# schematic_flex_sensor_driver.net
KiCad netlist of a schematic drawn in EAGLE
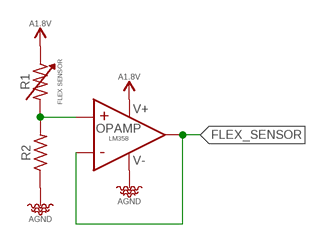
[diagram p0: schematic, sheet 1]

(export (version "E")
  (design (tool "Eeschema 10.0.6"))
  (components
    (comp (ref "OPAMP")
      (value "OPAMP_ILLUSTRATIVE")
      (footprint "eagle-import:SOT95P280X145-5")
      (libsource (lib "eagle-import") (part "OPAMP_ILLUSTRATIVE"))
    )
    (comp (ref "R1")
      (value "FLEX SENSOR")
      (footprint "eagle-import:PTH-CONNECTOR-2PIN")
      (fields
        (field (name "MFR") "TT Electronics/BI")
        (field (name "MPN") "P160KN2-0QA25B10K")
        (field (name "CREATOR") "MrSwirlyEyes")
      )
      (libsource (lib "eagle-import") (part "VARIABLE_PTH_10K-1/5W-20%_ACTLEN-25_OFFBOARD"))
    )
    (comp (ref "R2")
      (value "10K")
      (footprint "eagle-import:RESC1005X35_SMD-0402")
      (fields (field (name "MFR") "Yageo") (field (name "MPN") "RC0402JR-0710KP"))
      (libsource (lib "eagle-import") (part "10KΩ_SMD-0402_1/16W-5%"))
    )
  )
  (nets
    (net (code "1") (name "A1.8V") (class "Default")
      (node (ref "OPAMP") (pin "4") (pinfunction "V+_4") (pintype "passive"))
      (node (ref "R1") (pin "1") (pinfunction "1_1") (pintype "passive"))
    )
    (net (code "2") (name "AGND") (class "Default")
      (node (ref "OPAMP") (pin "5") (pinfunction "V-_5") (pintype "passive"))
      (node (ref "R2") (pin "1") (pinfunction "1_1") (pintype "passive"))
    )
    (net (code "3") (name "FLEX_SENSOR") (class "Default")
      (node (ref "OPAMP") (pin "2") (pinfunction "IN-_2") (pintype "input"))
      (node (ref "OPAMP") (pin "3") (pinfunction "OUT_3") (pintype "output"))
    )
    (net (code "4") (name "Net-(OPAMP-IN+)") (class "Default")
      (node (ref "OPAMP") (pin "1") (pinfunction "IN+_1") (pintype "input"))
      (node (ref "R1") (pin "2") (pinfunction "2_2") (pintype "passive"))
      (node (ref "R2") (pin "2") (pinfunction "2_2") (pintype "passive"))
    )
  )
)
